# uSD_Card_Interface.net
KiCad netlist of a schematic drawn in Altium Designer
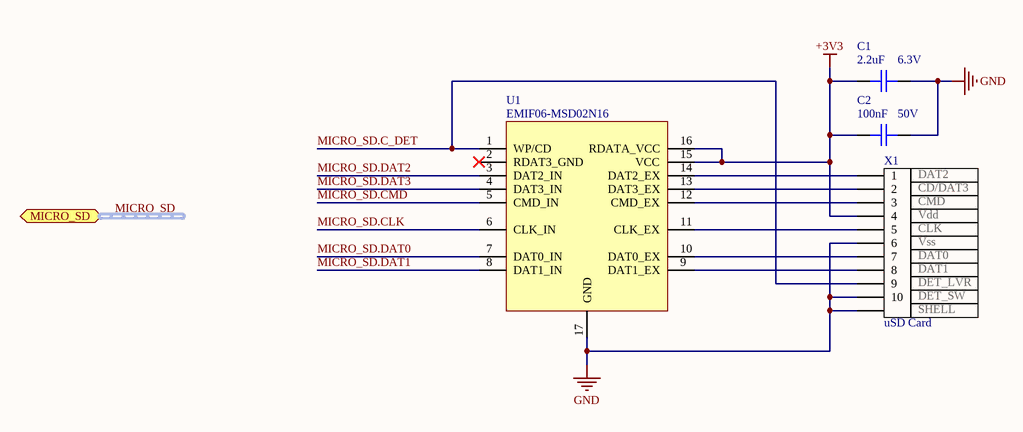
[diagram p0: uSD Card Interface.SchDoc]

(export (version "E")
  (design (tool "Eeschema 10.0.6"))
  (components
    (comp (ref "C1")
      (value "CAP CER 2.2UF 6.3V X5R 0402")
      (footprint "C0402")
      (description "2.2µF ±20% 6.3V Ceramic Capacitor X5R 0402 (1005 Metric)")
      (fields
        (field (name "MANUFACTURER") "Murata")
        (field (name "MANUFACTURER PART NUMBER") "GRM155R60J225ME15D")
        (field (name "CAPACITANCE") "2.2uF")
        (field (name "VOLTAGE") "6.3V")
      )
      (libsource (lib "capacitors_smd") (part "CAP CER 2.2UF 6.3V X5R 0402"))
    )
    (comp (ref "C2")
      (value "CAP CER 0.1UF 50V X7R 0402")
      (footprint "C0402")
      (description "0.1µF ±10% 50V Ceramic Capacitor X7R 0402 (1005 Metric)")
      (fields
        (field (name "MANUFACTURER") "TDK")
        (field (name "MANUFACTURER PART NUMBER") "CGA2B3X7R1H104K050BB")
        (field (name "CAPACITANCE") "100nF")
        (field (name "VOLTAGE") "50V")
      )
      (libsource (lib "capacitors_smd") (part "CAP CER 0.1UF 50V X7R 0402"))
    )
    (comp (ref "U1")
      (value "EMIF06-MSD02N16")
      (footprint "QFN 3.5x1.2-16L")
      (description "RC (Pi) EMI Filter 2nd Order Low Pass 6 Channel R = 45Ohms, C = 20pF (Total)  16-UFDFN Exposed Pad")
      (fields (field (name "MANUFACTURER") "STMicroelectronics"))
      (libsource (lib "diodes_tvs") (part "FILTER RC(PI) 45 OHM/20PF SMD"))
    )
    (comp (ref "X1")
      (value "uSD Card")
      (footprint "5025700893")
      (description "10 (8 + 2) Position Card Connector Secure Digital - microSD™ Surface Mount, Right Angle Gold")
      (fields
        (field (name "MANUFACTURER") "Molex")
        (field (name "MANUFACTURER PART NUMBER") "5025700893")
        (field (name "PIN_1") "DAT2")
        (field (name "PIN_2") "CD/DAT3")
        (field (name "PIN_3") "CMD")
        (field (name "PIN_4") "Vdd")
        (field (name "PIN_5") "CLK")
        (field (name "PIN_6") "Vss")
        (field (name "PIN_7") "DAT0")
        (field (name "PIN_8") "DAT1")
        (field (name "PIN_9") "DET_LVR")
        (field (name "PIN_10") "DET_SW")
        (field (name "PIN_0") "SHELL")
      )
      (libsource (lib "connectors_slots") (part "CONN MICRO SD CARD PUSH-PUSH R/A"))
    )
  )
  (nets
    (net (code "2") (name "+3V3") (class "Default")
      (node (ref "C1") (pin "2") (pinfunction "2_2") (pintype "passive"))
      (node (ref "C2") (pin "2") (pinfunction "2_2") (pintype "passive"))
      (node (ref "U1") (pin "15") (pinfunction "VCC_15") (pintype "power_in"))
      (node (ref "U1") (pin "16") (pinfunction "RDATA_VCC_16") (pintype "power_in"))
      (node (ref "X1") (pin "4") (pinfunction "4_4") (pintype "passive"))
    )
    (net (code "3") (name "/MICRO_SD.CLK") (class "Default")
      (node (ref "U1") (pin "6") (pinfunction "CLK_IN_6") (pintype "passive"))
    )
    (net (code "4") (name "/MICRO_SD.CMD") (class "Default")
      (node (ref "U1") (pin "5") (pinfunction "CMD_IN_5") (pintype "passive"))
    )
    (net (code "5") (name "/MICRO_SD.C_DET") (class "Default")
      (node (ref "U1") (pin "1") (pinfunction "WP/CD_1") (pintype "passive"))
      (node (ref "X1") (pin "9") (pinfunction "9_9") (pintype "passive"))
    )
    (net (code "6") (name "/MICRO_SD.DAT0") (class "Default")
      (node (ref "U1") (pin "7") (pinfunction "DAT0_IN_7") (pintype "passive"))
    )
    (net (code "7") (name "/MICRO_SD.DAT1") (class "Default")
      (node (ref "U1") (pin "8") (pinfunction "DAT1_IN_8") (pintype "passive"))
    )
    (net (code "8") (name "/MICRO_SD.DAT2") (class "Default")
      (node (ref "U1") (pin "3") (pinfunction "DAT2_IN_3") (pintype "passive"))
    )
    (net (code "9") (name "/MICRO_SD.DAT3") (class "Default")
      (node (ref "U1") (pin "4") (pinfunction "DAT3_IN_4") (pintype "passive"))
    )
    (net (code "11") (name "GND") (class "Default")
      (node (ref "C1") (pin "1") (pinfunction "1_1") (pintype "passive"))
      (node (ref "C2") (pin "1") (pinfunction "1_1") (pintype "passive"))
      (node (ref "U1") (pin "17") (pinfunction "GND_17") (pintype "power_in"))
      (node (ref "X1") (pin "0") (pinfunction "0_0") (pintype "power_in"))
      (node (ref "X1") (pin "10") (pinfunction "10_10") (pintype "passive"))
      (node (ref "X1") (pin "6") (pinfunction "6_6") (pintype "passive"))
    )
    (net (code "12") (name "Net-(U1-CLK_EX)") (class "Default")
      (node (ref "U1") (pin "11") (pinfunction "CLK_EX_11") (pintype "passive"))
      (node (ref "X1") (pin "5") (pinfunction "5_5") (pintype "passive"))
    )
    (net (code "13") (name "Net-(U1-CMD_EX)") (class "Default")
      (node (ref "U1") (pin "12") (pinfunction "CMD_EX_12") (pintype "passive"))
      (node (ref "X1") (pin "3") (pinfunction "3_3") (pintype "passive"))
    )
    (net (code "14") (name "Net-(U1-DAT0_EX)") (class "Default")
      (node (ref "U1") (pin "10") (pinfunction "DAT0_EX_10") (pintype "passive"))
      (node (ref "X1") (pin "7") (pinfunction "7_7") (pintype "passive"))
    )
    (net (code "15") (name "Net-(U1-DAT1_EX)") (class "Default")
      (node (ref "U1") (pin "9") (pinfunction "DAT1_EX_9") (pintype "passive"))
      (node (ref "X1") (pin "8") (pinfunction "8_8") (pintype "passive"))
    )
    (net (code "16") (name "Net-(U1-DAT2_EX)") (class "Default")
      (node (ref "U1") (pin "14") (pinfunction "DAT2_EX_14") (pintype "passive"))
      (node (ref "X1") (pin "1") (pinfunction "1_1") (pintype "passive"))
    )
    (net (code "17") (name "Net-(U1-DAT3_EX)") (class "Default")
      (node (ref "U1") (pin "13") (pinfunction "DAT3_EX_13") (pintype "passive"))
      (node (ref "X1") (pin "2") (pinfunction "2_2") (pintype "passive"))
    )
    (net (code "18") (name "unconnected-(U1-RDAT3_GND-Pad2)") (class "Default")
      (node (ref "U1") (pin "2") (pinfunction "RDAT3_GND_2") (pintype "passive+no_connect"))
    )
  )
)
